# ultrasoon_sensor.net
KiCad netlist of a schematic drawn in Altium Designer
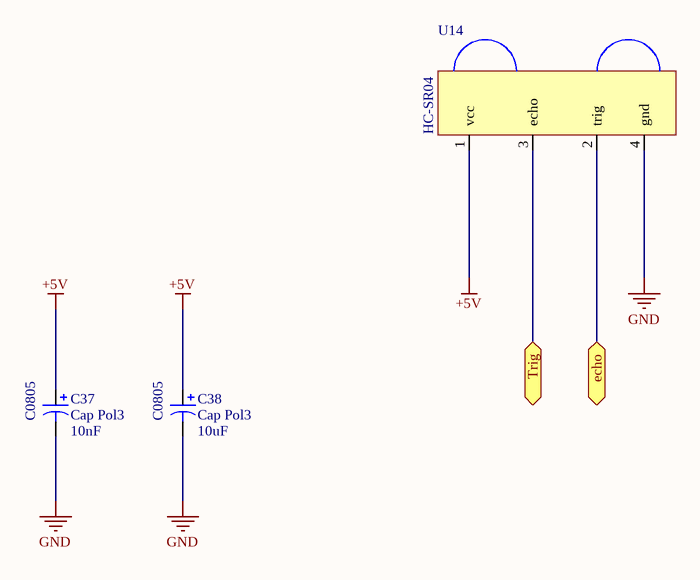
[diagram p0: ultrasoon sensor.SchDoc]

(export (version "E")
  (design (tool "Eeschema 10.0.6"))
  (components
    (comp (ref "C37")
      (value "Cap Pol3")
      (footprint "C0805")
      (description "Polarized Capacitor (Surface Mount)")
      (fields
        (field (name "PACKAGEREFERENCE") "C0805")
        (field (name "ALTIUM_VALUE") "10nF")
        (field (name "PUBLISHER") "Altium Limited")
      )
      (libsource (lib "Miscellaneous Devices") (part "Cap Pol3"))
    )
    (comp (ref "C38")
      (value "Cap Pol3")
      (footprint "C0805")
      (description "Polarized Capacitor (Surface Mount)")
      (fields
        (field (name "PACKAGEREFERENCE") "C0805")
        (field (name "ALTIUM_VALUE") "10uF")
        (field (name "PUBLISHER") "Altium Limited")
      )
      (libsource (lib "Miscellaneous Devices") (part "Cap Pol3"))
    )
    (comp (ref "U14")
      (value "HC-SR04")
      (footprint "ultrasoonSensor")
      (libsource (lib "ultrasoon") (part "HC-SR04"))
    )
  )
  (nets
    (net (code "1") (name "+5V") (class "Default")
      (node (ref "C37") (pin "1") (pinfunction "1_1") (pintype "passive"))
      (node (ref "C38") (pin "1") (pinfunction "1_1") (pintype "passive"))
      (node (ref "U14") (pin "1") (pinfunction "vcc_1") (pintype "passive"))
    )
    (net (code "2") (name "/Trig") (class "Default")
      (node (ref "U14") (pin "3") (pinfunction "echo_3") (pintype "passive"))
    )
    (net (code "3") (name "/echo") (class "Default")
      (node (ref "U14") (pin "2") (pinfunction "trig_2") (pintype "passive"))
    )
    (net (code "4") (name "GND") (class "Default")
      (node (ref "C37") (pin "2") (pinfunction "2_2") (pintype "passive"))
      (node (ref "C38") (pin "2") (pinfunction "2_2") (pintype "passive"))
      (node (ref "U14") (pin "4") (pinfunction "gnd_4") (pintype "passive"))
    )
  )
)
